# EFR732.net
KiCad netlist of a schematic drawn in EAGLE
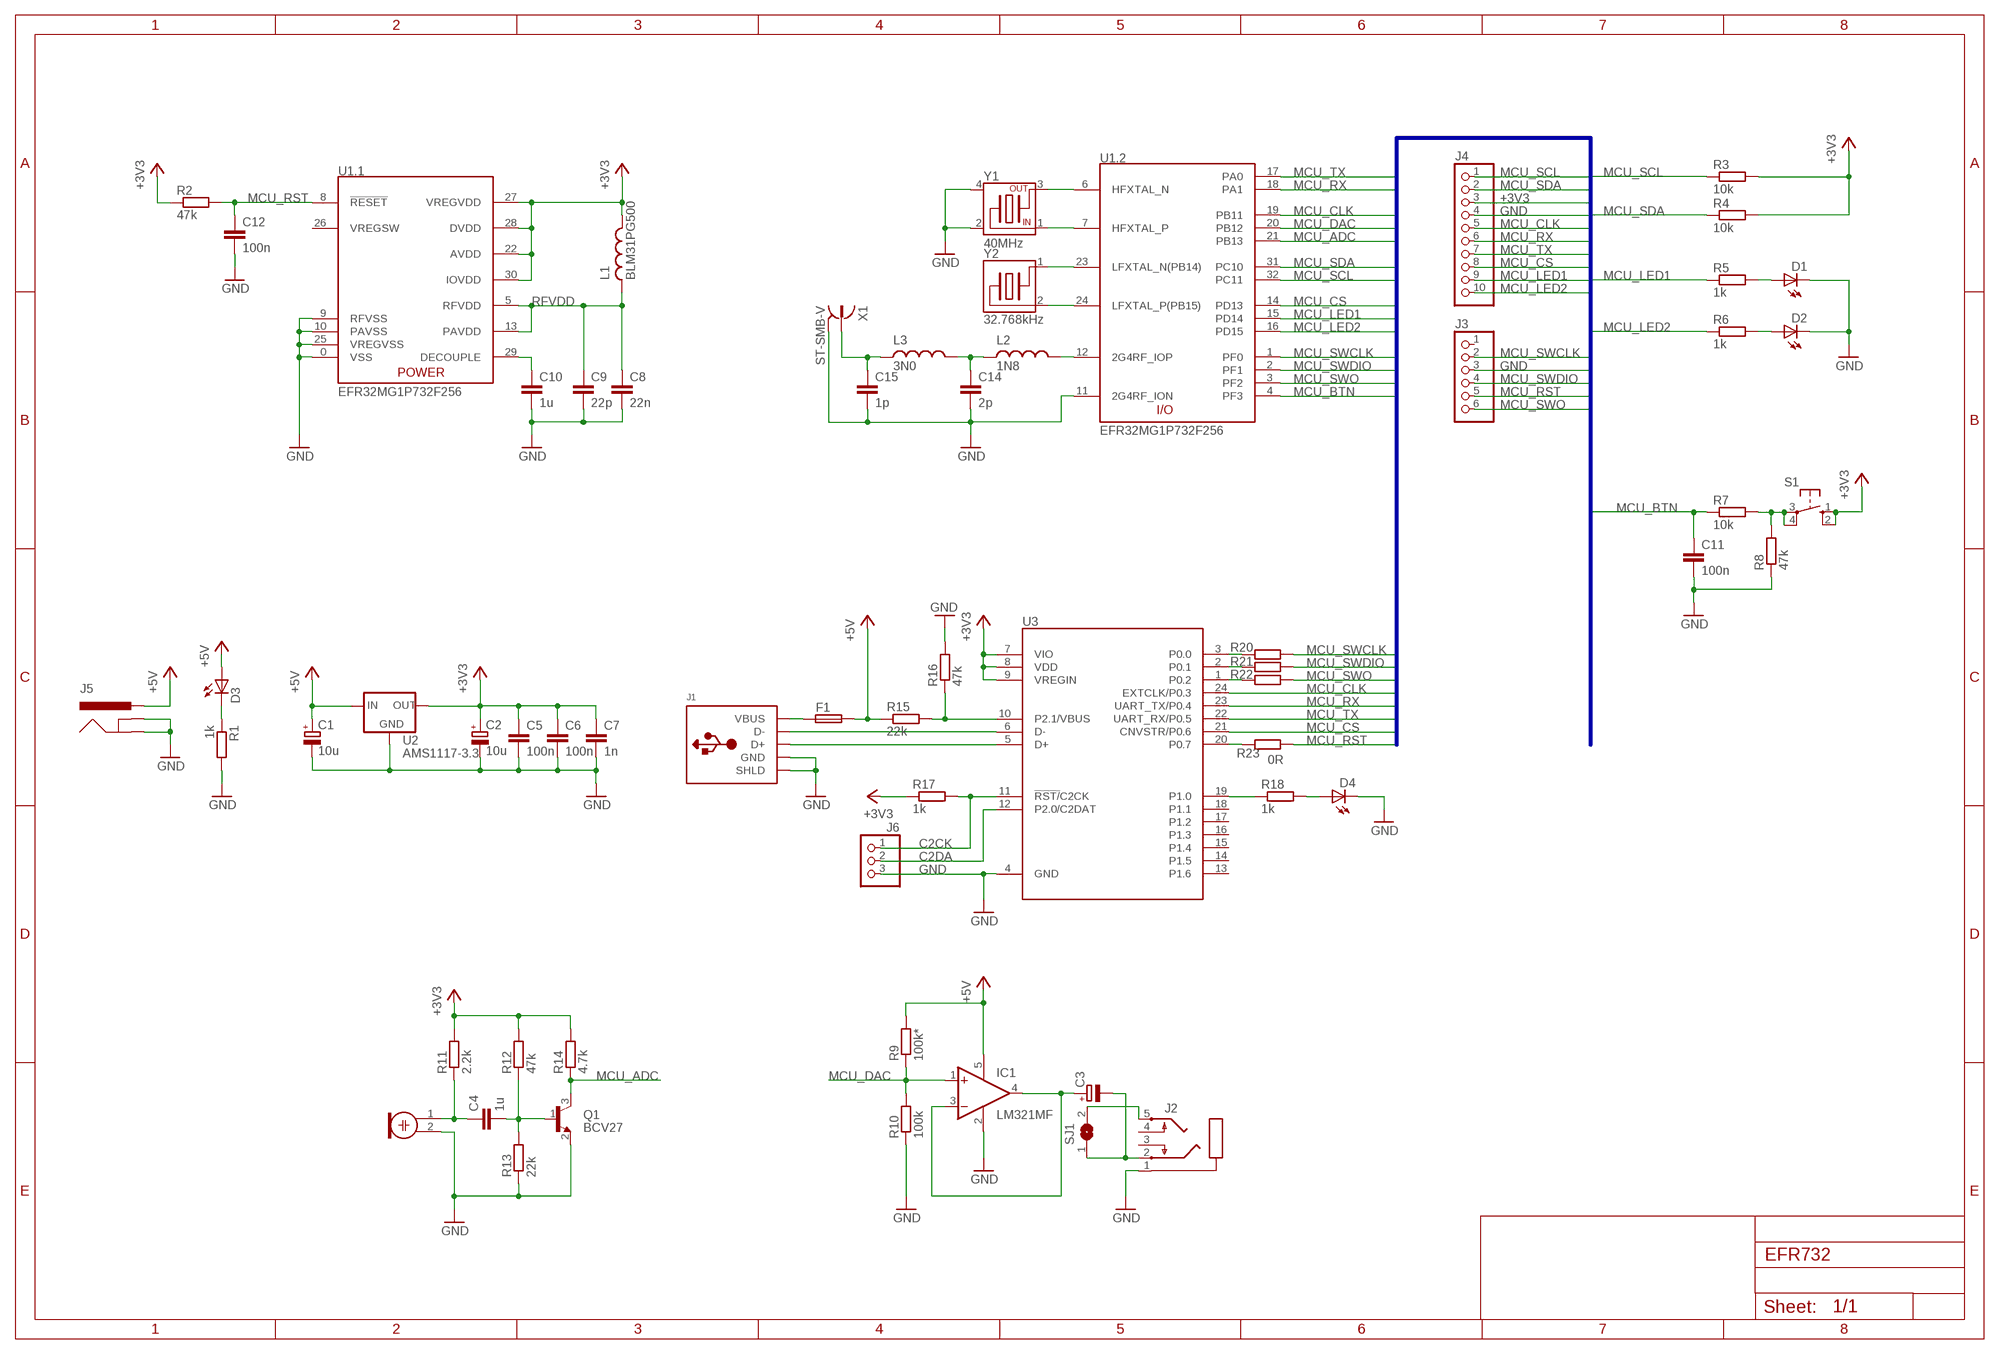
[diagram p0: schematic, sheet 1]

(export (version "E")
  (design (tool "Eeschema 10.0.6"))
  (components
    (comp (ref "C1")
      (value "10u")
      (footprint "eagle-import:RCL-1206F-POL")
      (libsource (lib "eagle-import") (part "CPOL-EU"))
    )
    (comp (ref "C2")
      (value "10u")
      (footprint "eagle-import:RCL-1206F-POL")
      (libsource (lib "eagle-import") (part "CPOL-EU"))
    )
    (comp (ref "C3")
      (value "CPOL-EU")
      (footprint "eagle-import:RCL-1206F-POL")
      (libsource (lib "eagle-import") (part "CPOL-EU"))
    )
    (comp (ref "C4")
      (value "1u")
      (footprint "eagle-import:RCL-1206F")
      (libsource (lib "eagle-import") (part "C-EU1206"))
    )
    (comp (ref "C5")
      (value "100n")
      (footprint "eagle-import:RCL-0805F")
      (libsource (lib "eagle-import") (part "C-EU0805"))
    )
    (comp (ref "C6")
      (value "100n")
      (footprint "eagle-import:RCL-0805F")
      (libsource (lib "eagle-import") (part "C-EU0805"))
    )
    (comp (ref "C7")
      (value "1n")
      (footprint "eagle-import:RCL-0805F")
      (libsource (lib "eagle-import") (part "C-EU0805"))
    )
    (comp (ref "C8")
      (value "22n")
      (footprint "eagle-import:RCL-0805F")
      (libsource (lib "eagle-import") (part "C-EU0805"))
    )
    (comp (ref "C9")
      (value "22p")
      (footprint "eagle-import:RCL-0805F")
      (libsource (lib "eagle-import") (part "C-EU0805"))
    )
    (comp (ref "C10")
      (value "1u")
      (footprint "eagle-import:RCL-1206F")
      (libsource (lib "eagle-import") (part "C-EU1206"))
    )
    (comp (ref "C11")
      (value "100n")
      (footprint "eagle-import:RCL-0805F")
      (libsource (lib "eagle-import") (part "C-EU0805"))
    )
    (comp (ref "C12")
      (value "100n")
      (footprint "eagle-import:RCL-0805F")
      (libsource (lib "eagle-import") (part "C-EU0805"))
    )
    (comp (ref "C14")
      (value "2p")
      (footprint "eagle-import:RCL-0805F")
      (libsource (lib "eagle-import") (part "C-EU0805"))
    )
    (comp (ref "C15")
      (value "1p")
      (footprint "eagle-import:RCL-0805F")
      (libsource (lib "eagle-import") (part "C-EU0805"))
    )
    (comp (ref "D1")
      (value "LED1206")
      (footprint "eagle-import:LED-1206F")
      (libsource (lib "eagle-import") (part "LED1206"))
    )
    (comp (ref "D2")
      (value "LED1206")
      (footprint "eagle-import:LED-1206F")
      (libsource (lib "eagle-import") (part "LED1206"))
    )
    (comp (ref "D3")
      (value "LED1206")
      (footprint "eagle-import:LED-1206F")
      (libsource (lib "eagle-import") (part "LED1206"))
    )
    (comp (ref "D4")
      (value "LED1206")
      (footprint "eagle-import:LED-1206F")
      (libsource (lib "eagle-import") (part "LED1206"))
    )
    (comp (ref "F1")
      (value "FUSE-NSMF")
      (footprint "eagle-import:RCL-1206F")
      (libsource (lib "eagle-import") (part "FUSE-NSMF"))
    )
    (comp (ref "IC1")
      (value "LM321MF")
      (footprint "eagle-import:SOT23-5")
      (libsource (lib "eagle-import") (part "LM321?MF"))
    )
    (comp (ref "J1")
      (value "USB-TYPE-B")
      (footprint "eagle-import:USB-TYPE-B-4P")
      (libsource (lib "eagle-import") (part "USB-TYPE-B"))
    )
    (comp (ref "J2")
      (value "AUDIO-JACK-3.5MM")
      (footprint "eagle-import:AUDIO-PG203J")
      (libsource (lib "eagle-import") (part "AUDIO-JACK-3.5MM"))
    )
    (comp (ref "J3")
      (value "PINH-1X06")
      (footprint "eagle-import:PINH-1X06")
      (libsource (lib "eagle-import") (part "PINH-1X06"))
    )
    (comp (ref "J4")
      (value "PINH-1X10")
      (footprint "eagle-import:PINH-1X10")
      (libsource (lib "eagle-import") (part "PINH-1X10"))
    )
    (comp (ref "J5")
      (value "POWER_JACK")
      (footprint "eagle-import:POWER_JACK_PTH")
      (libsource (lib "eagle-import") (part "POWER_JACK"))
    )
    (comp (ref "J6")
      (value "PINHD-1X3")
      (footprint "eagle-import:1X03")
      (libsource (lib "eagle-import") (part "PINHD-1X3"))
    )
    (comp (ref "L1")
      (value "BLM31PG500")
      (footprint "eagle-import:RCL-1206F")
      (libsource (lib "eagle-import") (part "L-EU1206"))
    )
    (comp (ref "L2")
      (value "1N8")
      (footprint "eagle-import:RCL-0603F")
      (libsource (lib "eagle-import") (part "L-EU"))
    )
    (comp (ref "L3")
      (value "3N0")
      (footprint "eagle-import:RCL-0603F")
      (libsource (lib "eagle-import") (part "L-EU"))
    )
    (comp (ref "M1")
      (value "ELECTRET_MICROPHON-WM-62PC/62PK")
      (footprint "eagle-import:WM-62PC_62PK")
      (libsource (lib "eagle-import") (part "ELECTRET_MICROPHON-WM-62PC/62PK"))
    )
    (comp (ref "Q1")
      (value "BCV27")
      (footprint "eagle-import:SOT23")
      (libsource (lib "eagle-import") (part "TR-NPN"))
    )
    (comp (ref "R1")
      (value "1k")
      (footprint "eagle-import:RCL-0805F")
      (libsource (lib "eagle-import") (part "R-EU0805"))
    )
    (comp (ref "R2")
      (value "47k")
      (footprint "eagle-import:RCL-0805F")
      (libsource (lib "eagle-import") (part "R-EU0805"))
    )
    (comp (ref "R3")
      (value "10k")
      (footprint "eagle-import:RCL-0805F")
      (libsource (lib "eagle-import") (part "R-EU0805"))
    )
    (comp (ref "R4")
      (value "10k")
      (footprint "eagle-import:RCL-0805F")
      (libsource (lib "eagle-import") (part "R-EU0805"))
    )
    (comp (ref "R5")
      (value "1k")
      (footprint "eagle-import:RCL-0805F")
      (libsource (lib "eagle-import") (part "R-EU0805"))
    )
    (comp (ref "R6")
      (value "1k")
      (footprint "eagle-import:RCL-0805F")
      (libsource (lib "eagle-import") (part "R-EU0805"))
    )
    (comp (ref "R7")
      (value "10k")
      (footprint "eagle-import:RCL-0805F")
      (libsource (lib "eagle-import") (part "R-EU0805"))
    )
    (comp (ref "R8")
      (value "47k")
      (footprint "eagle-import:RCL-0805F")
      (libsource (lib "eagle-import") (part "R-EU0805"))
    )
    (comp (ref "R9")
      (value "100k*")
      (footprint "eagle-import:RCL-0805F")
      (libsource (lib "eagle-import") (part "R-EU0805"))
    )
    (comp (ref "R10")
      (value "100k")
      (footprint "eagle-import:RCL-0805F")
      (libsource (lib "eagle-import") (part "R-EU0805"))
    )
    (comp (ref "R11")
      (value "2.2k")
      (footprint "eagle-import:RCL-0805F")
      (libsource (lib "eagle-import") (part "R-EU0805"))
    )
    (comp (ref "R12")
      (value "47k")
      (footprint "eagle-import:RCL-0805F")
      (libsource (lib "eagle-import") (part "R-EU0805"))
    )
    (comp (ref "R13")
      (value "22k")
      (footprint "eagle-import:RCL-0805F")
      (libsource (lib "eagle-import") (part "R-EU0805"))
    )
    (comp (ref "R14")
      (value "4.7k")
      (footprint "eagle-import:RCL-0805F")
      (libsource (lib "eagle-import") (part "R-EU0805"))
    )
    (comp (ref "R15")
      (value "22k")
      (footprint "eagle-import:RCL-0805F")
      (libsource (lib "eagle-import") (part "R-EU0805"))
    )
    (comp (ref "R16")
      (value "47k")
      (footprint "eagle-import:RCL-0805F")
      (libsource (lib "eagle-import") (part "R-EU0805"))
    )
    (comp (ref "R17")
      (value "1k")
      (footprint "eagle-import:RCL-0805F")
      (libsource (lib "eagle-import") (part "R-EU0805"))
    )
    (comp (ref "R18")
      (value "1k")
      (footprint "eagle-import:RCL-0805F")
      (libsource (lib "eagle-import") (part "R-EU0805"))
    )
    (comp (ref "R20")
      (value "R-EU0805")
      (footprint "eagle-import:RCL-0805F")
      (libsource (lib "eagle-import") (part "R-EU0805"))
    )
    (comp (ref "R21")
      (value "R-EU0805")
      (footprint "eagle-import:RCL-0805F")
      (libsource (lib "eagle-import") (part "R-EU0805"))
    )
    (comp (ref "R22")
      (value "R-EU0805")
      (footprint "eagle-import:RCL-0805F")
      (libsource (lib "eagle-import") (part "R-EU0805"))
    )
    (comp (ref "R23")
      (value "0R")
      (footprint "eagle-import:RCL-0805F")
      (libsource (lib "eagle-import") (part "R-EU0805"))
    )
    (comp (ref "S1")
      (value "SWITCH-10-XX")
      (footprint "eagle-import:BUTTON-B3F-10XX")
      (fields (field (name "MPN") "B3F-1000"))
      (libsource (lib "eagle-import") (part "SWITCH-10-XX"))
    )
    (comp (ref "SJ1") (value "SJ") (footprint "eagle-import:SJ") (libsource (lib "eagle-import") (part "SJ")))
    (comp (ref "U1")
      (value "EFR32MG1P732F256")
      (footprint "eagle-import:QFN32_5X5MM_EFR32MG1")
      (libsource (lib "eagle-import") (part "EFR32MG1P732-QFN32"))
    )
    (comp (ref "U2")
      (value "AMS1117-3.3")
      (footprint "eagle-import:SOT223")
      (libsource (lib "eagle-import") (part "AMS1117-3.3"))
    )
    (comp (ref "U3")
      (value "EFM8UB31F40G-QSOP24")
      (footprint "eagle-import:QSOP24-3.9X8.65MM")
      (libsource (lib "eagle-import") (part "EFM8UB31F40G-QSOP24"))
    )
    (comp (ref "X1")
      (value "ST-SMB-V")
      (footprint "eagle-import:ST-SMB-V")
      (libsource (lib "eagle-import") (part "ST-SMB-V"))
    )
    (comp (ref "Y1")
      (value "40MHz")
      (footprint "eagle-import:XTAL-FA-238")
      (libsource (lib "eagle-import") (part "CRYSTAL-FA-238R"))
    )
    (comp (ref "Y2")
      (value "32.768kHz")
      (footprint "eagle-import:XTAL-FC-135")
      (libsource (lib "eagle-import") (part "CRYSTAL-FC-135R"))
    )
  )
  (nets
    (net (code "1") (name "+3V3") (class "Default")
      (node (ref "C2") (pin "+") (pinfunction "+_+") (pintype "passive"))
      (node (ref "C5") (pin "1") (pinfunction "1_1") (pintype "passive"))
      (node (ref "C6") (pin "1") (pinfunction "1_1") (pintype "passive"))
      (node (ref "C7") (pin "1") (pinfunction "1_1") (pintype "passive"))
      (node (ref "J4") (pin "3") (pinfunction "3_3") (pintype "passive"))
      (node (ref "L1") (pin "2") (pinfunction "2_2") (pintype "passive"))
      (node (ref "R11") (pin "2") (pinfunction "2_2") (pintype "passive"))
      (node (ref "R12") (pin "2") (pinfunction "2_2") (pintype "passive"))
      (node (ref "R14") (pin "2") (pinfunction "2_2") (pintype "passive"))
      (node (ref "R17") (pin "1") (pinfunction "1_1") (pintype "passive"))
      (node (ref "R2") (pin "1") (pinfunction "1_1") (pintype "passive"))
      (node (ref "R3") (pin "2") (pinfunction "2_2") (pintype "passive"))
      (node (ref "R4") (pin "2") (pinfunction "2_2") (pintype "passive"))
      (node (ref "S1") (pin "1") (pinfunction "S_1") (pintype "passive"))
      (node (ref "S1") (pin "2") (pinfunction "S1_2") (pintype "passive"))
      (node (ref "U1") (pin "22") (pinfunction "AVDD_22") (pintype "power_in"))
      (node (ref "U1") (pin "27") (pinfunction "VREGVDD_27") (pintype "power_in"))
      (node (ref "U1") (pin "28") (pinfunction "DVDD_28") (pintype "power_in"))
      (node (ref "U1") (pin "30") (pinfunction "IOVDD_30") (pintype "power_in"))
      (node (ref "U2") (pin "2") (pinfunction "OUT_2") (pintype "passive"))
      (node (ref "U2") (pin "4") (pinfunction "OUT_4") (pintype "passive"))
      (node (ref "U3") (pin "7") (pinfunction "VIO_7") (pintype "power_in"))
      (node (ref "U3") (pin "8") (pinfunction "VDD_8") (pintype "power_in"))
      (node (ref "U3") (pin "9") (pinfunction "VREGIN_9") (pintype "power_in"))
    )
    (net (code "2") (name "+5V") (class "Default")
      (node (ref "C1") (pin "+") (pinfunction "+_+") (pintype "passive"))
      (node (ref "D3") (pin "A") (pinfunction "A_A") (pintype "passive"))
      (node (ref "F1") (pin "2") (pinfunction "2_2") (pintype "passive"))
      (node (ref "IC1") (pin "5") (pinfunction "V+_5") (pintype "power_in"))
      (node (ref "J5") (pin "PWR") (pinfunction "PWR_PWR") (pintype "bidirectional"))
      (node (ref "R15") (pin "1") (pinfunction "1_1") (pintype "passive"))
      (node (ref "R9") (pin "2") (pinfunction "2_2") (pintype "passive"))
      (node (ref "U2") (pin "3") (pinfunction "IN_3") (pintype "input"))
    )
    (net (code "3") (name "/C2CK") (class "Default")
      (node (ref "J6") (pin "1") (pinfunction "1_1") (pintype "passive"))
      (node (ref "R17") (pin "2") (pinfunction "2_2") (pintype "passive"))
      (node (ref "U3") (pin "11") (pinfunction "~{RST/}C2CK_11") (pintype "bidirectional"))
    )
    (net (code "4") (name "/C2DA") (class "Default")
      (node (ref "J6") (pin "2") (pinfunction "2_2") (pintype "passive"))
      (node (ref "U3") (pin "12") (pinfunction "P2.0/C2DAT_12") (pintype "bidirectional"))
    )
    (net (code "5") (name "/MCU_ADC") (class "Default")
      (node (ref "Q1") (pin "3") (pinfunction "C_3") (pintype "passive"))
      (node (ref "R14") (pin "1") (pinfunction "1_1") (pintype "passive"))
      (node (ref "U1") (pin "21") (pinfunction "PB13_21") (pintype "bidirectional"))
    )
    (net (code "6") (name "/MCU_BTN") (class "Default")
      (node (ref "C11") (pin "1") (pinfunction "1_1") (pintype "passive"))
      (node (ref "R7") (pin "1") (pinfunction "1_1") (pintype "passive"))
      (node (ref "U1") (pin "4") (pinfunction "PF3_4") (pintype "bidirectional"))
    )
    (net (code "7") (name "/MCU_CLK") (class "Default")
      (node (ref "J4") (pin "5") (pinfunction "5_5") (pintype "passive"))
      (node (ref "U1") (pin "19") (pinfunction "PB11_19") (pintype "bidirectional"))
      (node (ref "U3") (pin "24") (pinfunction "EXTCLK/P0.3_24") (pintype "bidirectional"))
    )
    (net (code "8") (name "/MCU_CS") (class "Default")
      (node (ref "J4") (pin "8") (pinfunction "8_8") (pintype "passive"))
      (node (ref "U1") (pin "14") (pinfunction "PD13_14") (pintype "bidirectional"))
      (node (ref "U3") (pin "21") (pinfunction "CNVSTR/P0.6_21") (pintype "bidirectional"))
    )
    (net (code "9") (name "/MCU_DAC") (class "Default")
      (node (ref "IC1") (pin "1") (pinfunction "+IN_1") (pintype "input"))
      (node (ref "R10") (pin "2") (pinfunction "2_2") (pintype "passive"))
      (node (ref "R9") (pin "1") (pinfunction "1_1") (pintype "passive"))
      (node (ref "U1") (pin "20") (pinfunction "PB12_20") (pintype "bidirectional"))
    )
    (net (code "10") (name "/MCU_LED1") (class "Default")
      (node (ref "J4") (pin "9") (pinfunction "9_9") (pintype "passive"))
      (node (ref "R5") (pin "1") (pinfunction "1_1") (pintype "passive"))
      (node (ref "U1") (pin "15") (pinfunction "PD14_15") (pintype "bidirectional"))
    )
    (net (code "11") (name "/MCU_LED2") (class "Default")
      (node (ref "J4") (pin "10") (pinfunction "10_10") (pintype "passive"))
      (node (ref "R6") (pin "1") (pinfunction "1_1") (pintype "passive"))
      (node (ref "U1") (pin "16") (pinfunction "PD15_16") (pintype "bidirectional"))
    )
    (net (code "12") (name "/MCU_RST") (class "Default")
      (node (ref "C12") (pin "1") (pinfunction "1_1") (pintype "passive"))
      (node (ref "J3") (pin "5") (pinfunction "5_5") (pintype "passive"))
      (node (ref "R2") (pin "2") (pinfunction "2_2") (pintype "passive"))
      (node (ref "R23") (pin "2") (pinfunction "2_2") (pintype "passive"))
      (node (ref "U1") (pin "8") (pinfunction "~{RESET}_8") (pintype "bidirectional"))
    )
    (net (code "13") (name "/MCU_RX") (class "Default")
      (node (ref "J4") (pin "6") (pinfunction "6_6") (pintype "passive"))
      (node (ref "U1") (pin "18") (pinfunction "PA1_18") (pintype "bidirectional"))
      (node (ref "U3") (pin "23") (pinfunction "UART_TX/P0.4_23") (pintype "bidirectional"))
    )
    (net (code "14") (name "/MCU_SCL") (class "Default")
      (node (ref "J4") (pin "1") (pinfunction "1_1") (pintype "passive"))
      (node (ref "R3") (pin "1") (pinfunction "1_1") (pintype "passive"))
      (node (ref "U1") (pin "32") (pinfunction "PC11_32") (pintype "bidirectional"))
    )
    (net (code "15") (name "/MCU_SDA") (class "Default")
      (node (ref "J4") (pin "2") (pinfunction "2_2") (pintype "passive"))
      (node (ref "R4") (pin "1") (pinfunction "1_1") (pintype "passive"))
      (node (ref "U1") (pin "31") (pinfunction "PC10_31") (pintype "bidirectional"))
    )
    (net (code "16") (name "/MCU_SWCLK") (class "Default")
      (node (ref "J3") (pin "2") (pinfunction "2_2") (pintype "passive"))
      (node (ref "R20") (pin "2") (pinfunction "2_2") (pintype "passive"))
      (node (ref "U1") (pin "1") (pinfunction "PF0_1") (pintype "bidirectional"))
    )
    (net (code "17") (name "/MCU_SWDIO") (class "Default")
      (node (ref "J3") (pin "4") (pinfunction "4_4") (pintype "passive"))
      (node (ref "R21") (pin "2") (pinfunction "2_2") (pintype "passive"))
      (node (ref "U1") (pin "2") (pinfunction "PF1_2") (pintype "bidirectional"))
    )
    (net (code "18") (name "/MCU_SWO") (class "Default")
      (node (ref "J3") (pin "6") (pinfunction "6_6") (pintype "passive"))
      (node (ref "R22") (pin "2") (pinfunction "2_2") (pintype "passive"))
      (node (ref "U1") (pin "3") (pinfunction "PF2_3") (pintype "bidirectional"))
    )
    (net (code "19") (name "/MCU_TX") (class "Default")
      (node (ref "J4") (pin "7") (pinfunction "7_7") (pintype "passive"))
      (node (ref "U1") (pin "17") (pinfunction "PA0_17") (pintype "bidirectional"))
      (node (ref "U3") (pin "22") (pinfunction "UART_RX/P0.5_22") (pintype "bidirectional"))
    )
    (net (code "20") (name "/RFVDD") (class "Default")
      (node (ref "C8") (pin "1") (pinfunction "1_1") (pintype "passive"))
      (node (ref "C9") (pin "1") (pinfunction "1_1") (pintype "passive"))
      (node (ref "L1") (pin "1") (pinfunction "1_1") (pintype "passive"))
      (node (ref "U1") (pin "13") (pinfunction "PAVDD_13") (pintype "power_in"))
      (node (ref "U1") (pin "5") (pinfunction "RFVDD_5") (pintype "power_in"))
    )
    (net (code "21") (name "/VREGSW") (class "Default")
      (node (ref "U1") (pin "26") (pinfunction "VREGSW_26") (pintype "power_in"))
    )
    (net (code "22") (name "GND") (class "Default")
      (node (ref "C1") (pin "-") (pinfunction "-_-") (pintype "passive"))
      (node (ref "C10") (pin "2") (pinfunction "2_2") (pintype "passive"))
      (node (ref "C11") (pin "2") (pinfunction "2_2") (pintype "passive"))
      (node (ref "C12") (pin "2") (pinfunction "2_2") (pintype "passive"))
      (node (ref "C14") (pin "2") (pinfunction "2_2") (pintype "passive"))
      (node (ref "C15") (pin "2") (pinfunction "2_2") (pintype "passive"))
      (node (ref "C2") (pin "-") (pinfunction "-_-") (pintype "passive"))
      (node (ref "C5") (pin "2") (pinfunction "2_2") (pintype "passive"))
      (node (ref "C6") (pin "2") (pinfunction "2_2") (pintype "passive"))
      (node (ref "C7") (pin "2") (pinfunction "2_2") (pintype "passive"))
      (node (ref "C8") (pin "2") (pinfunction "2_2") (pintype "passive"))
      (node (ref "C9") (pin "2") (pinfunction "2_2") (pintype "passive"))
      (node (ref "D1") (pin "C") (pinfunction "C_C") (pintype "passive"))
      (node (ref "D2") (pin "C") (pinfunction "C_C") (pintype "passive"))
      (node (ref "D4") (pin "C") (pinfunction "C_C") (pintype "passive"))
      (node (ref "IC1") (pin "2") (pinfunction "V-_2") (pintype "power_in"))
      (node (ref "J1") (pin "4_GND") (pinfunction "GND_4_GND") (pintype "power_in"))
      (node (ref "J1") (pin "M1") (pinfunction "SHLD_M1") (pintype "power_in"))
      (node (ref "J1") (pin "M2") (pinfunction "SHLD_M2") (pintype "power_in"))
      (node (ref "J2") (pin "1") (pinfunction "1_1") (pintype "passive"))
      (node (ref "J3") (pin "3") (pinfunction "3_3") (pintype "passive"))
      (node (ref "J4") (pin "4") (pinfunction "4_4") (pintype "passive"))
      (node (ref "J5") (pin "GND") (pinfunction "GND_GND") (pintype "bidirectional"))
      (node (ref "J5") (pin "GNDBREAK") (pinfunction "GNDBREAK_GNDBREAK") (pintype "bidirectional"))
      (node (ref "J6") (pin "3") (pinfunction "3_3") (pintype "passive"))
      (node (ref "M1") (pin "2") (pinfunction "2_2") (pintype "passive"))
      (node (ref "Q1") (pin "2") (pinfunction "E_2") (pintype "passive"))
      (node (ref "R1") (pin "2") (pinfunction "2_2") (pintype "passive"))
      (node (ref "R10") (pin "1") (pinfunction "1_1") (pintype "passive"))
      (node (ref "R13") (pin "1") (pinfunction "1_1") (pintype "passive"))
      (node (ref "R16") (pin "2") (pinfunction "2_2") (pintype "passive"))
      (node (ref "R8") (pin "1") (pinfunction "1_1") (pintype "passive"))
      (node (ref "U1") (pin "0") (pinfunction "VSS_0") (pintype "power_in"))
      (node (ref "U1") (pin "10") (pinfunction "PAVSS_10") (pintype "power_in"))
      (node (ref "U1") (pin "11") (pinfunction "2G4RF_ION_11") (pintype "bidirectional"))
      (node (ref "U1") (pin "25") (pinfunction "VREGVSS_25") (pintype "power_in"))
      (node (ref "U1") (pin "9") (pinfunction "RFVSS_9") (pintype "power_in"))
      (node (ref "U2") (pin "1") (pinfunction "GND_1") (pintype "input"))
      (node (ref "U3") (pin "4") (pinfunction "GND_4") (pintype "power_in"))
      (node (ref "X1") (pin "2") (pinfunction "2_2") (pintype "passive"))
      (node (ref "X1") (pin "3") (pinfunction "2_3") (pintype "passive"))
      (node (ref "X1") (pin "4") (pinfunction "2_4") (pintype "passive"))
      (node (ref "X1") (pin "5") (pinfunction "2_5") (pintype "passive"))
      (node (ref "Y1") (pin "2") (pinfunction "2_2") (pintype "bidirectional"))
      (node (ref "Y1") (pin "4") (pinfunction "4_4") (pintype "bidirectional"))
    )
    (net (code "23") (name "Net-(C3-Pad-)") (class "Default")
      (node (ref "C3") (pin "-") (pinfunction "-_-") (pintype "passive"))
      (node (ref "J2") (pin "2") (pinfunction "2_2") (pintype "passive"))
      (node (ref "SJ1") (pin "1") (pinfunction "1_1") (pintype "passive"))
    )
    (net (code "24") (name "Net-(C4-Pad1)") (class "Default")
      (node (ref "C4") (pin "1") (pinfunction "1_1") (pintype "passive"))
      (node (ref "M1") (pin "1") (pinfunction "1_1") (pintype "passive"))
      (node (ref "R11") (pin "1") (pinfunction "1_1") (pintype "passive"))
    )
    (net (code "25") (name "Net-(C14-Pad1)") (class "Default")
      (node (ref "C14") (pin "1") (pinfunction "1_1") (pintype "passive"))
      (node (ref "L2") (pin "1") (pinfunction "1_1") (pintype "passive"))
      (node (ref "L3") (pin "2") (pinfunction "2_2") (pintype "passive"))
    )
    (net (code "26") (name "Net-(C15-Pad1)") (class "Default")
      (node (ref "C15") (pin "1") (pinfunction "1_1") (pintype "passive"))
      (node (ref "L3") (pin "1") (pinfunction "1_1") (pintype "passive"))
      (node (ref "X1") (pin "1") (pinfunction "1_1") (pintype "passive"))
    )
    (net (code "27") (name "Net-(D1-PadA)") (class "Default")
      (node (ref "D1") (pin "A") (pinfunction "A_A") (pintype "passive"))
      (node (ref "R5") (pin "2") (pinfunction "2_2") (pintype "passive"))
    )
    (net (code "28") (name "Net-(D2-PadA)") (class "Default")
      (node (ref "D2") (pin "A") (pinfunction "A_A") (pintype "passive"))
      (node (ref "R6") (pin "2") (pinfunction "2_2") (pintype "passive"))
    )
    (net (code "29") (name "Net-(D3-PadC)") (class "Default")
      (node (ref "D3") (pin "C") (pinfunction "C_C") (pintype "passive"))
      (node (ref "R1") (pin "1") (pinfunction "1_1") (pintype "passive"))
    )
    (net (code "30") (name "Net-(D4-PadA)") (class "Default")
      (node (ref "D4") (pin "A") (pinfunction "A_A") (pintype "passive"))
      (node (ref "R18") (pin "2") (pinfunction "2_2") (pintype "passive"))
    )
    (net (code "31") (name "Net-(IC1--IN)") (class "Default")
      (node (ref "C3") (pin "+") (pinfunction "+_+") (pintype "passive"))
      (node (ref "IC1") (pin "3") (pinfunction "-IN_3") (pintype "input"))
      (node (ref "IC1") (pin "4") (pinfunction "OUT_4") (pintype "output"))
    )
    (net (code "32") (name "Net-(J1-D+)") (class "Default")
      (node (ref "J1") (pin "3_DP") (pinfunction "D+_3_DP") (pintype "bidirectional"))
      (node (ref "U3") (pin "5") (pinfunction "D+_5") (pintype "bidirectional"))
    )
    (net (code "33") (name "Net-(J1-D-)") (class "Default")
      (node (ref "J1") (pin "2_DM") (pinfunction "D-_2_DM") (pintype "bidirectional"))
      (node (ref "U3") (pin "6") (pinfunction "D-_6") (pintype "bidirectional"))
    )
    (net (code "34") (name "Net-(J1-VBUS)") (class "Default")
      (node (ref "F1") (pin "1") (pinfunction "1_1") (pintype "passive"))
      (node (ref "J1") (pin "1_VBUS") (pinfunction "VBUS_1_VBUS") (pintype "power_in"))
    )
    (net (code "35") (name "Net-(J2-Pad5)") (class "Default")
      (node (ref "J2") (pin "5") (pinfunction "5_5") (pintype "passive"))
      (node (ref "SJ1") (pin "2") (pinfunction "2_2") (pintype "passive"))
    )
    (net (code "36") (name "Net-(Q1-B)") (class "Default")
      (node (ref "C4") (pin "2") (pinfunction "2_2") (pintype "passive"))
      (node (ref "Q1") (pin "1") (pinfunction "B_1") (pintype "passive"))
      (node (ref "R12") (pin "1") (pinfunction "1_1") (pintype "passive"))
      (node (ref "R13") (pin "2") (pinfunction "2_2") (pintype "passive"))
    )
    (net (code "37") (name "Net-(S1-P)") (class "Default")
      (node (ref "R7") (pin "2") (pinfunction "2_2") (pintype "passive"))
      (node (ref "R8") (pin "2") (pinfunction "2_2") (pintype "passive"))
      (node (ref "S1") (pin "3") (pinfunction "P_3") (pintype "passive"))
      (node (ref "S1") (pin "4") (pinfunction "P1_4") (pintype "passive"))
    )
    (net (code "38") (name "Net-(U1A-DECOUPLE)") (class "Default")
      (node (ref "C10") (pin "1") (pinfunction "1_1") (pintype "passive"))
      (node (ref "U1") (pin "29") (pinfunction "DECOUPLE_29") (pintype "power_in"))
    )
    (net (code "39") (name "Net-(U1B-2G4RF_IOP)") (class "Default")
      (node (ref "L2") (pin "2") (pinfunction "2_2") (pintype "passive"))
      (node (ref "U1") (pin "12") (pinfunction "2G4RF_IOP_12") (pintype "bidirectional"))
    )
    (net (code "40") (name "Net-(U1B-HFXTAL_N)") (class "Default")
      (node (ref "U1") (pin "6") (pinfunction "HFXTAL_N_6") (pintype "bidirectional"))
      (node (ref "Y1") (pin "3") (pinfunction "X.OUT_3") (pintype "bidirectional"))
    )
    (net (code "41") (name "Net-(U1B-HFXTAL_P)") (class "Default")
      (node (ref "U1") (pin "7") (pinfunction "HFXTAL_P_7") (pintype "bidirectional"))
      (node (ref "Y1") (pin "1") (pinfunction "X.IN_1") (pintype "bidirectional"))
    )
    (net (code "42") (name "Net-(U1B-LFXTAL_N(PB14))") (class "Default")
      (node (ref "U1") (pin "23") (pinfunction "LFXTAL_N(PB14)_23") (pintype "bidirectional"))
      (node (ref "Y2") (pin "1") (pinfunction "1.XIN_1") (pintype "bidirectional"))
    )
    (net (code "43") (name "Net-(U1B-LFXTAL_P(PB15))") (class "Default")
      (node (ref "U1") (pin "24") (pinfunction "LFXTAL_P(PB15)_24") (pintype "bidirectional"))
      (node (ref "Y2") (pin "2") (pinfunction "2.XIN_2") (pintype "bidirectional"))
    )
    (net (code "44") (name "Net-(U3-P0.0)") (class "Default")
      (node (ref "R20") (pin "1") (pinfunction "1_1") (pintype "passive"))
      (node (ref "U3") (pin "3") (pinfunction "P0.0_3") (pintype "bidirectional"))
    )
    (net (code "45") (name "Net-(U3-P0.1)") (class "Default")
      (node (ref "R21") (pin "1") (pinfunction "1_1") (pintype "passive"))
      (node (ref "U3") (pin "2") (pinfunction "P0.1_2") (pintype "bidirectional"))
    )
    (net (code "46") (name "Net-(U3-P0.2)") (class "Default")
      (node (ref "R22") (pin "1") (pinfunction "1_1") (pintype "passive"))
      (node (ref "U3") (pin "1") (pinfunction "P0.2_1") (pintype "bidirectional"))
    )
    (net (code "47") (name "Net-(U3-P0.7)") (class "Default")
      (node (ref "R23") (pin "1") (pinfunction "1_1") (pintype "passive"))
      (node (ref "U3") (pin "20") (pinfunction "P0.7_20") (pintype "bidirectional"))
    )
    (net (code "48") (name "Net-(U3-P1.0)") (class "Default")
      (node (ref "R18") (pin "1") (pinfunction "1_1") (pintype "passive"))
      (node (ref "U3") (pin "19") (pinfunction "P1.0_19") (pintype "bidirectional"))
    )
    (net (code "49") (name "Net-(U3-P2.1{slash}VBUS)") (class "Default")
      (node (ref "R15") (pin "2") (pinfunction "2_2") (pintype "passive"))
      (node (ref "R16") (pin "1") (pinfunction "1_1") (pintype "passive"))
      (node (ref "U3") (pin "10") (pinfunction "P2.1/VBUS_10") (pintype "bidirectional"))
    )
    (net (code "50") (name "unconnected-(J2-Pad3)") (class "Default")
      (node (ref "J2") (pin "3") (pinfunction "3_3") (pintype "passive"))
    )
    (net (code "51") (name "unconnected-(J2-Pad4)") (class "Default")
      (node (ref "J2") (pin "4") (pinfunction "4_4") (pintype "passive"))
    )
    (net (code "52") (name "unconnected-(J3-Pad1)") (class "Default")
      (node (ref "J3") (pin "1") (pinfunction "1_1") (pintype "passive"))
    )
    (net (code "53") (name "unconnected-(U3-P1.1-Pad18)") (class "Default")
      (node (ref "U3") (pin "18") (pinfunction "P1.1_18") (pintype "bidirectional"))
    )
    (net (code "54") (name "unconnected-(U3-P1.2-Pad17)") (class "Default")
      (node (ref "U3") (pin "17") (pinfunction "P1.2_17") (pintype "bidirectional"))
    )
    (net (code "55") (name "unconnected-(U3-P1.3-Pad16)") (class "Default")
      (node (ref "U3") (pin "16") (pinfunction "P1.3_16") (pintype "bidirectional"))
    )
    (net (code "56") (name "unconnected-(U3-P1.4-Pad15)") (class "Default")
      (node (ref "U3") (pin "15") (pinfunction "P1.4_15") (pintype "bidirectional"))
    )
    (net (code "57") (name "unconnected-(U3-P1.5-Pad14)") (class "Default")
      (node (ref "U3") (pin "14") (pinfunction "P1.5_14") (pintype "bidirectional"))
    )
    (net (code "58") (name "unconnected-(U3-P1.6-Pad13)") (class "Default")
      (node (ref "U3") (pin "13") (pinfunction "P1.6_13") (pintype "bidirectional"))
    )
  )
)
